# TE_Module_driver.net
KiCad netlist of a schematic drawn in EAGLE
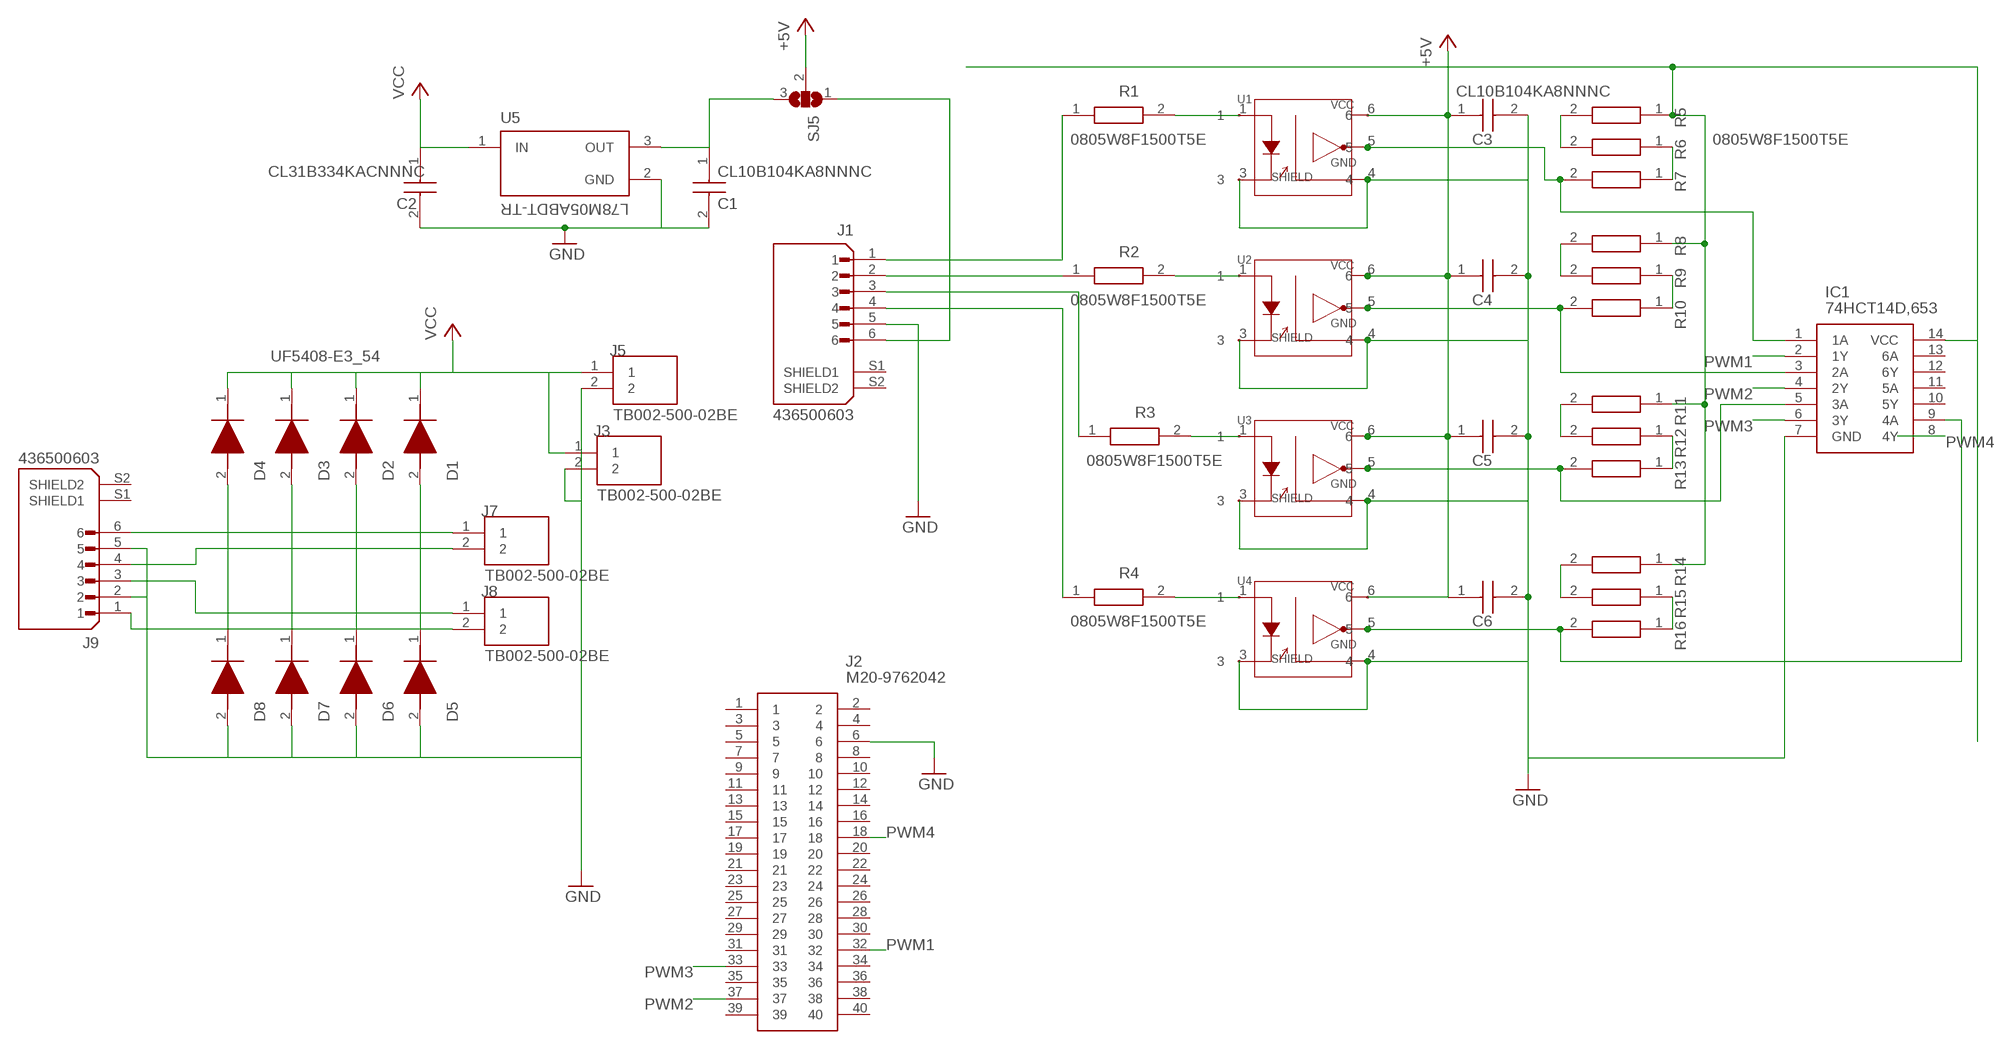
[diagram p0: schematic, sheet 1]

(export (version "E")
  (design (tool "Eeschema 10.0.6"))
  (components
    (comp (ref "C1")
      (value "CL10B104KA8NNNC")
      (footprint "eagle-import:CAPC1608X90N")
      (fields (field (name "LCSC_PART") "C1590") (field (name "MOUSER_PART_NUMBER") "187-CL10B104KA8NNNC"))
      (libsource (lib "eagle-import") (part "CL10B104KA8NNNC"))
    )
    (comp (ref "C2")
      (value "CL31B334KACNNNC")
      (footprint "eagle-import:CAPC3216X140N")
      (fields (field (name "LCSC_PART") "C318760"))
      (libsource (lib "eagle-import") (part "CL31B334KACNNNC"))
    )
    (comp (ref "C3")
      (value "CL10B104KA8NNNC")
      (footprint "eagle-import:CAPC1608X90N")
      (fields (field (name "LCSC_PART") "C1590") (field (name "MOUSER_PART_NUMBER") "187-CL10B104KA8NNNC"))
      (libsource (lib "eagle-import") (part "CL10B104KA8NNNC"))
    )
    (comp (ref "C4")
      (value "CL10B104KA8NNNC")
      (footprint "eagle-import:CAPC1608X90N")
      (fields (field (name "LCSC_PART") "C1590") (field (name "MOUSER_PART_NUMBER") "187-CL10B104KA8NNNC"))
      (libsource (lib "eagle-import") (part "CL10B104KA8NNNC"))
    )
    (comp (ref "C5")
      (value "CL10B104KA8NNNC")
      (footprint "eagle-import:CAPC1608X90N")
      (fields (field (name "LCSC_PART") "C1590") (field (name "MOUSER_PART_NUMBER") "187-CL10B104KA8NNNC"))
      (libsource (lib "eagle-import") (part "CL10B104KA8NNNC"))
    )
    (comp (ref "C6")
      (value "CL10B104KA8NNNC")
      (footprint "eagle-import:CAPC1608X90N")
      (fields (field (name "LCSC_PART") "C1590") (field (name "MOUSER_PART_NUMBER") "187-CL10B104KA8NNNC"))
      (libsource (lib "eagle-import") (part "CL10B104KA8NNNC"))
    )
    (comp (ref "D1")
      (value "UF5408-E3_54")
      (footprint "eagle-import:DIOAD2855W132L835D505")
      (fields
        (field (name "ARROW_PART_NUMBER") "UF5408-E3/54")
        (field (name "MOUSER_PART_NUMBER") "625-UF5408-E3")
      )
      (libsource (lib "eagle-import") (part "UF5408-E3_54"))
    )
    (comp (ref "D2")
      (value "UF5408-E3_54")
      (footprint "eagle-import:DIOAD2855W132L835D505")
      (fields
        (field (name "ARROW_PART_NUMBER") "UF5408-E3/54")
        (field (name "MOUSER_PART_NUMBER") "625-UF5408-E3")
      )
      (libsource (lib "eagle-import") (part "UF5408-E3_54"))
    )
    (comp (ref "D3")
      (value "UF5408-E3_54")
      (footprint "eagle-import:DIOAD2855W132L835D505")
      (fields
        (field (name "ARROW_PART_NUMBER") "UF5408-E3/54")
        (field (name "MOUSER_PART_NUMBER") "625-UF5408-E3")
      )
      (libsource (lib "eagle-import") (part "UF5408-E3_54"))
    )
    (comp (ref "D4")
      (value "UF5408-E3_54")
      (footprint "eagle-import:DIOAD2855W132L835D505")
      (fields
        (field (name "ARROW_PART_NUMBER") "UF5408-E3/54")
        (field (name "MOUSER_PART_NUMBER") "625-UF5408-E3")
      )
      (libsource (lib "eagle-import") (part "UF5408-E3_54"))
    )
    (comp (ref "D5")
      (value "UF5408-E3_54")
      (footprint "eagle-import:DIOAD2855W132L835D505")
      (fields
        (field (name "ARROW_PART_NUMBER") "UF5408-E3/54")
        (field (name "MOUSER_PART_NUMBER") "625-UF5408-E3")
      )
      (libsource (lib "eagle-import") (part "UF5408-E3_54"))
    )
    (comp (ref "D6")
      (value "UF5408-E3_54")
      (footprint "eagle-import:DIOAD2855W132L835D505")
      (fields
        (field (name "ARROW_PART_NUMBER") "UF5408-E3/54")
        (field (name "MOUSER_PART_NUMBER") "625-UF5408-E3")
      )
      (libsource (lib "eagle-import") (part "UF5408-E3_54"))
    )
    (comp (ref "D7")
      (value "UF5408-E3_54")
      (footprint "eagle-import:DIOAD2855W132L835D505")
      (fields
        (field (name "ARROW_PART_NUMBER") "UF5408-E3/54")
        (field (name "MOUSER_PART_NUMBER") "625-UF5408-E3")
      )
      (libsource (lib "eagle-import") (part "UF5408-E3_54"))
    )
    (comp (ref "D8")
      (value "UF5408-E3_54")
      (footprint "eagle-import:DIOAD2855W132L835D505")
      (fields
        (field (name "ARROW_PART_NUMBER") "UF5408-E3/54")
        (field (name "MOUSER_PART_NUMBER") "625-UF5408-E3")
      )
      (libsource (lib "eagle-import") (part "UF5408-E3_54"))
    )
    (comp (ref "IC1")
      (value "74HCT14D,653")
      (footprint "eagle-import:SOIC127P600X175-14N")
      (fields (field (name "LCSC_PART") "C5967") (field (name "MOUSER_PART_NUMBER") "771-74HCT14D-T"))
      (libsource (lib "eagle-import") (part "74HCT14D,653"))
    )
    (comp (ref "J1")
      (value "436500603")
      (footprint "eagle-import:MOLEX_436500603")
      (fields (field (name "MANUFACTURER") "Molex"))
      (libsource (lib "eagle-import") (part "436500603"))
    )
    (comp (ref "J2")
      (value "M20-9762042")
      (footprint "eagle-import:HDRV40W64P254_2X20_5080X508X83")
      (fields (field (name "MOUSER_PART_NUMBER") "855-M20-9762042"))
      (libsource (lib "eagle-import") (part "M20-9762042"))
    )
    (comp (ref "J3")
      (value "TB002-500-02BE")
      (footprint "eagle-import:CUI_TB002-500-02BE")
      (fields (field (name "MANUFACTURER") "CUI"))
      (libsource (lib "eagle-import") (part "TB002-500-02BE"))
    )
    (comp (ref "J5")
      (value "TB002-500-02BE")
      (footprint "eagle-import:CUI_TB002-500-02BE")
      (fields (field (name "MANUFACTURER") "CUI"))
      (libsource (lib "eagle-import") (part "TB002-500-02BE"))
    )
    (comp (ref "J7")
      (value "TB002-500-02BE")
      (footprint "eagle-import:CUI_TB002-500-02BE")
      (fields (field (name "MANUFACTURER") "CUI"))
      (libsource (lib "eagle-import") (part "TB002-500-02BE"))
    )
    (comp (ref "J8")
      (value "TB002-500-02BE")
      (footprint "eagle-import:CUI_TB002-500-02BE")
      (fields (field (name "MANUFACTURER") "CUI"))
      (libsource (lib "eagle-import") (part "TB002-500-02BE"))
    )
    (comp (ref "J9")
      (value "436500603")
      (footprint "eagle-import:MOLEX_436500603")
      (fields (field (name "MANUFACTURER") "Molex"))
      (libsource (lib "eagle-import") (part "436500603"))
    )
    (comp (ref "R1")
      (value "0805W8F1500T5E")
      (footprint "eagle-import:RESC2013X65N")
      (fields (field (name "LCSC_PART") "C17471"))
      (libsource (lib "eagle-import") (part "0805W8F1500T5E"))
    )
    (comp (ref "R2")
      (value "0805W8F1500T5E")
      (footprint "eagle-import:RESC2013X65N")
      (fields (field (name "LCSC_PART") "C17471"))
      (libsource (lib "eagle-import") (part "0805W8F1500T5E"))
    )
    (comp (ref "R3")
      (value "0805W8F1500T5E")
      (footprint "eagle-import:RESC2013X65N")
      (fields (field (name "LCSC_PART") "C17471"))
      (libsource (lib "eagle-import") (part "0805W8F1500T5E"))
    )
    (comp (ref "R4")
      (value "0805W8F1500T5E")
      (footprint "eagle-import:RESC2013X65N")
      (fields (field (name "LCSC_PART") "C17471"))
      (libsource (lib "eagle-import") (part "0805W8F1500T5E"))
    )
    (comp (ref "R5")
      (value "0805W8F1500T5E")
      (footprint "eagle-import:RESC2013X65N")
      (fields (field (name "LCSC_PART") "C17471"))
      (libsource (lib "eagle-import") (part "0805W8F1500T5E"))
    )
    (comp (ref "R6")
      (value "0805W8F1500T5E")
      (footprint "eagle-import:RESC2013X65N")
      (fields (field (name "LCSC_PART") "C17471"))
      (libsource (lib "eagle-import") (part "0805W8F1500T5E"))
    )
    (comp (ref "R7")
      (value "0805W8F1500T5E")
      (footprint "eagle-import:RESC2013X65N")
      (fields (field (name "LCSC_PART") "C17471"))
      (libsource (lib "eagle-import") (part "0805W8F1500T5E"))
    )
    (comp (ref "R8")
      (value "0805W8F1500T5E")
      (footprint "eagle-import:RESC2013X65N")
      (fields (field (name "LCSC_PART") "C17471"))
      (libsource (lib "eagle-import") (part "0805W8F1500T5E"))
    )
    (comp (ref "R9")
      (value "0805W8F1500T5E")
      (footprint "eagle-import:RESC2013X65N")
      (fields (field (name "LCSC_PART") "C17471"))
      (libsource (lib "eagle-import") (part "0805W8F1500T5E"))
    )
    (comp (ref "R10")
      (value "0805W8F1500T5E")
      (footprint "eagle-import:RESC2013X65N")
      (fields (field (name "LCSC_PART") "C17471"))
      (libsource (lib "eagle-import") (part "0805W8F1500T5E"))
    )
    (comp (ref "R11")
      (value "0805W8F1500T5E")
      (footprint "eagle-import:RESC2013X65N")
      (fields (field (name "LCSC_PART") "C17471"))
      (libsource (lib "eagle-import") (part "0805W8F1500T5E"))
    )
    (comp (ref "R12")
      (value "0805W8F1500T5E")
      (footprint "eagle-import:RESC2013X65N")
      (fields (field (name "LCSC_PART") "C17471"))
      (libsource (lib "eagle-import") (part "0805W8F1500T5E"))
    )
    (comp (ref "R13")
      (value "0805W8F1500T5E")
      (footprint "eagle-import:RESC2013X65N")
      (fields (field (name "LCSC_PART") "C17471"))
      (libsource (lib "eagle-import") (part "0805W8F1500T5E"))
    )
    (comp (ref "R14")
      (value "0805W8F1500T5E")
      (footprint "eagle-import:RESC2013X65N")
      (fields (field (name "LCSC_PART") "C17471"))
      (libsource (lib "eagle-import") (part "0805W8F1500T5E"))
    )
    (comp (ref "R15")
      (value "0805W8F1500T5E")
      (footprint "eagle-import:RESC2013X65N")
      (fields (field (name "LCSC_PART") "C17471"))
      (libsource (lib "eagle-import") (part "0805W8F1500T5E"))
    )
    (comp (ref "R16")
      (value "0805W8F1500T5E")
      (footprint "eagle-import:RESC2013X65N")
      (fields (field (name "LCSC_PART") "C17471"))
      (libsource (lib "eagle-import") (part "0805W8F1500T5E"))
    )
    (comp (ref "SJ5")
      (value "SJ2W")
      (footprint "eagle-import:SJ_2")
      (libsource (lib "eagle-import") (part "SJ2W"))
    )
    (comp (ref "U1")
      (value "TLP2362(TPL,E(T")
      (footprint "eagle-import:5PIN_SO6_TOS")
      (fields
        (field (name "LCSC_PART") "C37658")
        (field (name "COPYRIGHT") "Copyright (C) 2022 Ultra Librarian. All rights reserved.")
      )
      (libsource (lib "eagle-import") (part "TLP2362(TPL,E(T"))
    )
    (comp (ref "U2")
      (value "TLP2362(TPL,E(T")
      (footprint "eagle-import:5PIN_SO6_TOS")
      (fields
        (field (name "LCSC_PART") "C37658")
        (field (name "COPYRIGHT") "Copyright (C) 2022 Ultra Librarian. All rights reserved.")
      )
      (libsource (lib "eagle-import") (part "TLP2362(TPL,E(T"))
    )
    (comp (ref "U3")
      (value "TLP2362(TPL,E(T")
      (footprint "eagle-import:5PIN_SO6_TOS")
      (fields
        (field (name "LCSC_PART") "C37658")
        (field (name "COPYRIGHT") "Copyright (C) 2022 Ultra Librarian. All rights reserved.")
      )
      (libsource (lib "eagle-import") (part "TLP2362(TPL,E(T"))
    )
    (comp (ref "U4")
      (value "TLP2362(TPL,E(T")
      (footprint "eagle-import:5PIN_SO6_TOS")
      (fields
        (field (name "LCSC_PART") "C37658")
        (field (name "COPYRIGHT") "Copyright (C) 2022 Ultra Librarian. All rights reserved.")
      )
      (libsource (lib "eagle-import") (part "TLP2362(TPL,E(T"))
    )
    (comp (ref "U5")
      (value "L78M05ABDT-TR")
      (footprint "eagle-import:VREG_L78M05ABDT-TR")
      (fields (field (name "LCSC_PART") "C58069") (field (name "MANUFACTURER") "STMicroelectronics"))
      (libsource (lib "eagle-import") (part "L78M05ABDT-TR"))
    )
  )
  (nets
    (net (code "1") (name "+5V") (class "Default")
      (node (ref "C3") (pin "1") (pinfunction "1_1") (pintype "bidirectional"))
      (node (ref "C4") (pin "1") (pinfunction "1_1") (pintype "bidirectional"))
      (node (ref "C5") (pin "1") (pinfunction "1_1") (pintype "bidirectional"))
      (node (ref "C6") (pin "1") (pinfunction "1_1") (pintype "bidirectional"))
      (node (ref "IC1") (pin "14") (pinfunction "VCC_14") (pintype "bidirectional"))
      (node (ref "R11") (pin "1") (pinfunction "1_1") (pintype "bidirectional"))
      (node (ref "R14") (pin "1") (pinfunction "1_1") (pintype "bidirectional"))
      (node (ref "R5") (pin "1") (pinfunction "1_1") (pintype "bidirectional"))
      (node (ref "R8") (pin "1") (pinfunction "1_1") (pintype "bidirectional"))
      (node (ref "SJ5") (pin "2") (pinfunction "2_2") (pintype "passive"))
      (node (ref "U1") (pin "6") (pinfunction "6_6") (pintype "passive"))
      (node (ref "U2") (pin "6") (pinfunction "6_6") (pintype "passive"))
      (node (ref "U3") (pin "6") (pinfunction "6_6") (pintype "passive"))
      (node (ref "U4") (pin "6") (pinfunction "6_6") (pintype "passive"))
    )
    (net (code "2") (name "/PWM1") (class "Default")
      (node (ref "IC1") (pin "2") (pinfunction "1Y_2") (pintype "bidirectional"))
      (node (ref "J2") (pin "32") (pinfunction "32_32") (pintype "bidirectional"))
    )
    (net (code "3") (name "/PWM2") (class "Default")
      (node (ref "IC1") (pin "4") (pinfunction "2Y_4") (pintype "bidirectional"))
      (node (ref "J2") (pin "37") (pinfunction "37_37") (pintype "bidirectional"))
    )
    (net (code "4") (name "/PWM3") (class "Default")
      (node (ref "IC1") (pin "6") (pinfunction "3Y_6") (pintype "bidirectional"))
      (node (ref "J2") (pin "33") (pinfunction "33_33") (pintype "bidirectional"))
    )
    (net (code "5") (name "/PWM4") (class "Default")
      (node (ref "IC1") (pin "8") (pinfunction "4Y_8") (pintype "bidirectional"))
      (node (ref "J2") (pin "18") (pinfunction "18_18") (pintype "bidirectional"))
    )
    (net (code "6") (name "GND") (class "Default")
      (node (ref "C1") (pin "2") (pinfunction "2_2") (pintype "bidirectional"))
      (node (ref "C2") (pin "2") (pinfunction "2_2") (pintype "bidirectional"))
      (node (ref "C3") (pin "2") (pinfunction "2_2") (pintype "bidirectional"))
      (node (ref "C4") (pin "2") (pinfunction "2_2") (pintype "bidirectional"))
      (node (ref "C5") (pin "2") (pinfunction "2_2") (pintype "bidirectional"))
      (node (ref "C6") (pin "2") (pinfunction "2_2") (pintype "bidirectional"))
      (node (ref "D5") (pin "2") (pinfunction "A_2") (pintype "bidirectional"))
      (node (ref "D6") (pin "2") (pinfunction "A_2") (pintype "bidirectional"))
      (node (ref "D7") (pin "2") (pinfunction "A_2") (pintype "bidirectional"))
      (node (ref "D8") (pin "2") (pinfunction "A_2") (pintype "bidirectional"))
      (node (ref "IC1") (pin "7") (pinfunction "GND_7") (pintype "bidirectional"))
      (node (ref "J1") (pin "5") (pinfunction "5_5") (pintype "passive"))
      (node (ref "J2") (pin "6") (pinfunction "6_6") (pintype "bidirectional"))
      (node (ref "J3") (pin "2") (pinfunction "2_2") (pintype "passive"))
      (node (ref "J5") (pin "2") (pinfunction "2_2") (pintype "passive"))
      (node (ref "J9") (pin "2") (pinfunction "2_2") (pintype "passive"))
      (node (ref "J9") (pin "5") (pinfunction "5_5") (pintype "passive"))
      (node (ref "U1") (pin "3") (pinfunction "3_3") (pintype "passive"))
      (node (ref "U1") (pin "4") (pinfunction "4_4") (pintype "passive"))
      (node (ref "U2") (pin "3") (pinfunction "3_3") (pintype "passive"))
      (node (ref "U2") (pin "4") (pinfunction "4_4") (pintype "passive"))
      (node (ref "U3") (pin "3") (pinfunction "3_3") (pintype "passive"))
      (node (ref "U3") (pin "4") (pinfunction "4_4") (pintype "passive"))
      (node (ref "U4") (pin "3") (pinfunction "3_3") (pintype "passive"))
      (node (ref "U4") (pin "4") (pinfunction "4_4") (pintype "passive"))
      (node (ref "U5") (pin "2") (pinfunction "GND_2") (pintype "power_in"))
    )
    (net (code "7") (name "Net-(D1-A)") (class "Default")
      (node (ref "D1") (pin "2") (pinfunction "A_2") (pintype "bidirectional"))
      (node (ref "D5") (pin "1") (pinfunction "K_1") (pintype "bidirectional"))
      (node (ref "J8") (pin "2") (pinfunction "2_2") (pintype "passive"))
      (node (ref "J9") (pin "1") (pinfunction "1_1") (pintype "passive"))
    )
    (net (code "8") (name "Net-(D2-A)") (class "Default")
      (node (ref "D2") (pin "2") (pinfunction "A_2") (pintype "bidirectional"))
      (node (ref "D6") (pin "1") (pinfunction "K_1") (pintype "bidirectional"))
      (node (ref "J8") (pin "1") (pinfunction "1_1") (pintype "passive"))
      (node (ref "J9") (pin "3") (pinfunction "3_3") (pintype "passive"))
    )
    (net (code "9") (name "Net-(D3-A)") (class "Default")
      (node (ref "D3") (pin "2") (pinfunction "A_2") (pintype "bidirectional"))
      (node (ref "D7") (pin "1") (pinfunction "K_1") (pintype "bidirectional"))
      (node (ref "J7") (pin "2") (pinfunction "2_2") (pintype "passive"))
      (node (ref "J9") (pin "4") (pinfunction "4_4") (pintype "passive"))
    )
    (net (code "10") (name "Net-(D4-A)") (class "Default")
      (node (ref "D4") (pin "2") (pinfunction "A_2") (pintype "bidirectional"))
      (node (ref "D8") (pin "1") (pinfunction "K_1") (pintype "bidirectional"))
      (node (ref "J7") (pin "1") (pinfunction "1_1") (pintype "passive"))
      (node (ref "J9") (pin "6") (pinfunction "6_6") (pintype "passive"))
    )
    (net (code "11") (name "Net-(IC1-1A)") (class "Default")
      (node (ref "IC1") (pin "1") (pinfunction "1A_1") (pintype "bidirectional"))
      (node (ref "R7") (pin "2") (pinfunction "2_2") (pintype "bidirectional"))
      (node (ref "U1") (pin "5") (pinfunction "5_5") (pintype "output"))
    )
    (net (code "12") (name "Net-(IC1-2A)") (class "Default")
      (node (ref "IC1") (pin "3") (pinfunction "2A_3") (pintype "bidirectional"))
      (node (ref "R10") (pin "2") (pinfunction "2_2") (pintype "bidirectional"))
      (node (ref "U2") (pin "5") (pinfunction "5_5") (pintype "output"))
    )
    (net (code "13") (name "Net-(IC1-3A)") (class "Default")
      (node (ref "IC1") (pin "5") (pinfunction "3A_5") (pintype "bidirectional"))
      (node (ref "R13") (pin "2") (pinfunction "2_2") (pintype "bidirectional"))
      (node (ref "U3") (pin "5") (pinfunction "5_5") (pintype "output"))
    )
    (net (code "14") (name "Net-(IC1-4A)") (class "Default")
      (node (ref "IC1") (pin "9") (pinfunction "4A_9") (pintype "bidirectional"))
      (node (ref "R16") (pin "2") (pinfunction "2_2") (pintype "bidirectional"))
      (node (ref "U4") (pin "5") (pinfunction "5_5") (pintype "output"))
    )
    (net (code "15") (name "Net-(J1-Pad1)") (class "Default")
      (node (ref "J1") (pin "1") (pinfunction "1_1") (pintype "passive"))
      (node (ref "R1") (pin "1") (pinfunction "1_1") (pintype "bidirectional"))
    )
    (net (code "16") (name "Net-(J1-Pad2)") (class "Default")
      (node (ref "J1") (pin "2") (pinfunction "2_2") (pintype "passive"))
      (node (ref "R2") (pin "1") (pinfunction "1_1") (pintype "bidirectional"))
    )
    (net (code "17") (name "Net-(J1-Pad3)") (class "Default")
      (node (ref "J1") (pin "3") (pinfunction "3_3") (pintype "passive"))
      (node (ref "R3") (pin "1") (pinfunction "1_1") (pintype "bidirectional"))
    )
    (net (code "18") (name "Net-(J1-Pad4)") (class "Default")
      (node (ref "J1") (pin "4") (pinfunction "4_4") (pintype "passive"))
      (node (ref "R4") (pin "1") (pinfunction "1_1") (pintype "bidirectional"))
    )
    (net (code "19") (name "Net-(J1-Pad6)") (class "Default")
      (node (ref "J1") (pin "6") (pinfunction "6_6") (pintype "passive"))
      (node (ref "SJ5") (pin "1") (pinfunction "1_1") (pintype "passive"))
    )
    (net (code "20") (name "Net-(R1-Pad2)") (class "Default")
      (node (ref "R1") (pin "2") (pinfunction "2_2") (pintype "bidirectional"))
      (node (ref "U1") (pin "1") (pinfunction "1_1") (pintype "passive"))
    )
    (net (code "21") (name "Net-(R2-Pad2)") (class "Default")
      (node (ref "R2") (pin "2") (pinfunction "2_2") (pintype "bidirectional"))
      (node (ref "U2") (pin "1") (pinfunction "1_1") (pintype "passive"))
    )
    (net (code "22") (name "Net-(R3-Pad2)") (class "Default")
      (node (ref "R3") (pin "2") (pinfunction "2_2") (pintype "bidirectional"))
      (node (ref "U3") (pin "1") (pinfunction "1_1") (pintype "passive"))
    )
    (net (code "23") (name "Net-(R4-Pad2)") (class "Default")
      (node (ref "R4") (pin "2") (pinfunction "2_2") (pintype "bidirectional"))
      (node (ref "U4") (pin "1") (pinfunction "1_1") (pintype "passive"))
    )
    (net (code "24") (name "Net-(R5-Pad2)") (class "Default")
      (node (ref "R5") (pin "2") (pinfunction "2_2") (pintype "bidirectional"))
      (node (ref "R6") (pin "2") (pinfunction "2_2") (pintype "bidirectional"))
    )
    (net (code "25") (name "Net-(R6-Pad1)") (class "Default")
      (node (ref "R6") (pin "1") (pinfunction "1_1") (pintype "bidirectional"))
      (node (ref "R7") (pin "1") (pinfunction "1_1") (pintype "bidirectional"))
    )
    (net (code "26") (name "Net-(R8-Pad2)") (class "Default")
      (node (ref "R8") (pin "2") (pinfunction "2_2") (pintype "bidirectional"))
      (node (ref "R9") (pin "2") (pinfunction "2_2") (pintype "bidirectional"))
    )
    (net (code "27") (name "Net-(R10-Pad1)") (class "Default")
      (node (ref "R10") (pin "1") (pinfunction "1_1") (pintype "bidirectional"))
      (node (ref "R9") (pin "1") (pinfunction "1_1") (pintype "bidirectional"))
    )
    (net (code "28") (name "Net-(R11-Pad2)") (class "Default")
      (node (ref "R11") (pin "2") (pinfunction "2_2") (pintype "bidirectional"))
      (node (ref "R12") (pin "2") (pinfunction "2_2") (pintype "bidirectional"))
    )
    (net (code "29") (name "Net-(R12-Pad1)") (class "Default")
      (node (ref "R12") (pin "1") (pinfunction "1_1") (pintype "bidirectional"))
      (node (ref "R13") (pin "1") (pinfunction "1_1") (pintype "bidirectional"))
    )
    (net (code "30") (name "Net-(R14-Pad2)") (class "Default")
      (node (ref "R14") (pin "2") (pinfunction "2_2") (pintype "bidirectional"))
      (node (ref "R15") (pin "2") (pinfunction "2_2") (pintype "bidirectional"))
    )
    (net (code "31") (name "Net-(R15-Pad1)") (class "Default")
      (node (ref "R15") (pin "1") (pinfunction "1_1") (pintype "bidirectional"))
      (node (ref "R16") (pin "1") (pinfunction "1_1") (pintype "bidirectional"))
    )
    (net (code "32") (name "Net-(U5-OUT)") (class "Default")
      (node (ref "C1") (pin "1") (pinfunction "1_1") (pintype "bidirectional"))
      (node (ref "SJ5") (pin "3") (pinfunction "3_3") (pintype "passive"))
      (node (ref "U5") (pin "3") (pinfunction "OUT_3") (pintype "output"))
    )
    (net (code "33") (name "VCC") (class "Default")
      (node (ref "C2") (pin "1") (pinfunction "1_1") (pintype "bidirectional"))
      (node (ref "D1") (pin "1") (pinfunction "K_1") (pintype "bidirectional"))
      (node (ref "D2") (pin "1") (pinfunction "K_1") (pintype "bidirectional"))
      (node (ref "D3") (pin "1") (pinfunction "K_1") (pintype "bidirectional"))
      (node (ref "D4") (pin "1") (pinfunction "K_1") (pintype "bidirectional"))
      (node (ref "J3") (pin "1") (pinfunction "1_1") (pintype "passive"))
      (node (ref "J5") (pin "1") (pinfunction "1_1") (pintype "passive"))
      (node (ref "U5") (pin "1") (pinfunction "IN_1") (pintype "input"))
    )
    (net (code "34") (name "unconnected-(IC1-5A-Pad11)") (class "Default")
      (node (ref "IC1") (pin "11") (pinfunction "5A_11") (pintype "bidirectional"))
    )
    (net (code "35") (name "unconnected-(IC1-5Y-Pad10)") (class "Default")
      (node (ref "IC1") (pin "10") (pinfunction "5Y_10") (pintype "bidirectional"))
    )
    (net (code "36") (name "unconnected-(IC1-6A-Pad13)") (class "Default")
      (node (ref "IC1") (pin "13") (pinfunction "6A_13") (pintype "bidirectional"))
    )
    (net (code "37") (name "unconnected-(IC1-6Y-Pad12)") (class "Default")
      (node (ref "IC1") (pin "12") (pinfunction "6Y_12") (pintype "bidirectional"))
    )
    (net (code "38") (name "unconnected-(J1-SHIELD1-PadS1)") (class "Default")
      (node (ref "J1") (pin "S1") (pinfunction "SHIELD1_S1") (pintype "passive"))
    )
    (net (code "39") (name "unconnected-(J1-SHIELD2-PadS2)") (class "Default")
      (node (ref "J1") (pin "S2") (pinfunction "SHIELD2_S2") (pintype "passive"))
    )
    (net (code "40") (name "unconnected-(J2-Pad1)") (class "Default")
      (node (ref "J2") (pin "1") (pinfunction "1_1") (pintype "bidirectional"))
    )
    (net (code "41") (name "unconnected-(J2-Pad2)") (class "Default")
      (node (ref "J2") (pin "2") (pinfunction "2_2") (pintype "bidirectional"))
    )
    (net (code "42") (name "unconnected-(J2-Pad3)") (class "Default")
      (node (ref "J2") (pin "3") (pinfunction "3_3") (pintype "bidirectional"))
    )
    (net (code "43") (name "unconnected-(J2-Pad4)") (class "Default")
      (node (ref "J2") (pin "4") (pinfunction "4_4") (pintype "bidirectional"))
    )
    (net (code "44") (name "unconnected-(J2-Pad5)") (class "Default")
      (node (ref "J2") (pin "5") (pinfunction "5_5") (pintype "bidirectional"))
    )
    (net (code "45") (name "unconnected-(J2-Pad7)") (class "Default")
      (node (ref "J2") (pin "7") (pinfunction "7_7") (pintype "bidirectional"))
    )
    (net (code "46") (name "unconnected-(J2-Pad8)") (class "Default")
      (node (ref "J2") (pin "8") (pinfunction "8_8") (pintype "bidirectional"))
    )
    (net (code "47") (name "unconnected-(J2-Pad9)") (class "Default")
      (node (ref "J2") (pin "9") (pinfunction "9_9") (pintype "bidirectional"))
    )
    (net (code "48") (name "unconnected-(J2-Pad10)") (class "Default")
      (node (ref "J2") (pin "10") (pinfunction "10_10") (pintype "bidirectional"))
    )
    (net (code "49") (name "unconnected-(J2-Pad11)") (class "Default")
      (node (ref "J2") (pin "11") (pinfunction "11_11") (pintype "bidirectional"))
    )
    (net (code "50") (name "unconnected-(J2-Pad12)") (class "Default")
      (node (ref "J2") (pin "12") (pinfunction "12_12") (pintype "bidirectional"))
    )
    (net (code "51") (name "unconnected-(J2-Pad13)") (class "Default")
      (node (ref "J2") (pin "13") (pinfunction "13_13") (pintype "bidirectional"))
    )
    (net (code "52") (name "unconnected-(J2-Pad14)") (class "Default")
      (node (ref "J2") (pin "14") (pinfunction "14_14") (pintype "bidirectional"))
    )
    (net (code "53") (name "unconnected-(J2-Pad15)") (class "Default")
      (node (ref "J2") (pin "15") (pinfunction "15_15") (pintype "bidirectional"))
    )
    (net (code "54") (name "unconnected-(J2-Pad16)") (class "Default")
      (node (ref "J2") (pin "16") (pinfunction "16_16") (pintype "bidirectional"))
    )
    (net (code "55") (name "unconnected-(J2-Pad17)") (class "Default")
      (node (ref "J2") (pin "17") (pinfunction "17_17") (pintype "bidirectional"))
    )
    (net (code "56") (name "unconnected-(J2-Pad19)") (class "Default")
      (node (ref "J2") (pin "19") (pinfunction "19_19") (pintype "bidirectional"))
    )
    (net (code "57") (name "unconnected-(J2-Pad20)") (class "Default")
      (node (ref "J2") (pin "20") (pinfunction "20_20") (pintype "bidirectional"))
    )
    (net (code "58") (name "unconnected-(J2-Pad21)") (class "Default")
      (node (ref "J2") (pin "21") (pinfunction "21_21") (pintype "bidirectional"))
    )
    (net (code "59") (name "unconnected-(J2-Pad22)") (class "Default")
      (node (ref "J2") (pin "22") (pinfunction "22_22") (pintype "bidirectional"))
    )
    (net (code "60") (name "unconnected-(J2-Pad23)") (class "Default")
      (node (ref "J2") (pin "23") (pinfunction "23_23") (pintype "bidirectional"))
    )
    (net (code "61") (name "unconnected-(J2-Pad24)") (class "Default")
      (node (ref "J2") (pin "24") (pinfunction "24_24") (pintype "bidirectional"))
    )
    (net (code "62") (name "unconnected-(J2-Pad25)") (class "Default")
      (node (ref "J2") (pin "25") (pinfunction "25_25") (pintype "bidirectional"))
    )
    (net (code "63") (name "unconnected-(J2-Pad26)") (class "Default")
      (node (ref "J2") (pin "26") (pinfunction "26_26") (pintype "bidirectional"))
    )
    (net (code "64") (name "unconnected-(J2-Pad27)") (class "Default")
      (node (ref "J2") (pin "27") (pinfunction "27_27") (pintype "bidirectional"))
    )
    (net (code "65") (name "unconnected-(J2-Pad28)") (class "Default")
      (node (ref "J2") (pin "28") (pinfunction "28_28") (pintype "bidirectional"))
    )
    (net (code "66") (name "unconnected-(J2-Pad29)") (class "Default")
      (node (ref "J2") (pin "29") (pinfunction "29_29") (pintype "bidirectional"))
    )
    (net (code "67") (name "unconnected-(J2-Pad30)") (class "Default")
      (node (ref "J2") (pin "30") (pinfunction "30_30") (pintype "bidirectional"))
    )
    (net (code "68") (name "unconnected-(J2-Pad31)") (class "Default")
      (node (ref "J2") (pin "31") (pinfunction "31_31") (pintype "bidirectional"))
    )
    (net (code "69") (name "unconnected-(J2-Pad34)") (class "Default")
      (node (ref "J2") (pin "34") (pinfunction "34_34") (pintype "bidirectional"))
    )
    (net (code "70") (name "unconnected-(J2-Pad35)") (class "Default")
      (node (ref "J2") (pin "35") (pinfunction "35_35") (pintype "bidirectional"))
    )
    (net (code "71") (name "unconnected-(J2-Pad36)") (class "Default")
      (node (ref "J2") (pin "36") (pinfunction "36_36") (pintype "bidirectional"))
    )
    (net (code "72") (name "unconnected-(J2-Pad38)") (class "Default")
      (node (ref "J2") (pin "38") (pinfunction "38_38") (pintype "bidirectional"))
    )
    (net (code "73") (name "unconnected-(J2-Pad39)") (class "Default")
      (node (ref "J2") (pin "39") (pinfunction "39_39") (pintype "bidirectional"))
    )
    (net (code "74") (name "unconnected-(J2-Pad40)") (class "Default")
      (node (ref "J2") (pin "40") (pinfunction "40_40") (pintype "bidirectional"))
    )
    (net (code "75") (name "unconnected-(J9-SHIELD1-PadS1)") (class "Default")
      (node (ref "J9") (pin "S1") (pinfunction "SHIELD1_S1") (pintype "passive"))
    )
    (net (code "76") (name "unconnected-(J9-SHIELD2-PadS2)") (class "Default")
      (node (ref "J9") (pin "S2") (pinfunction "SHIELD2_S2") (pintype "passive"))
    )
  )
)
